# farolasbasura.net
KiCad netlist of a schematic drawn in EAGLE
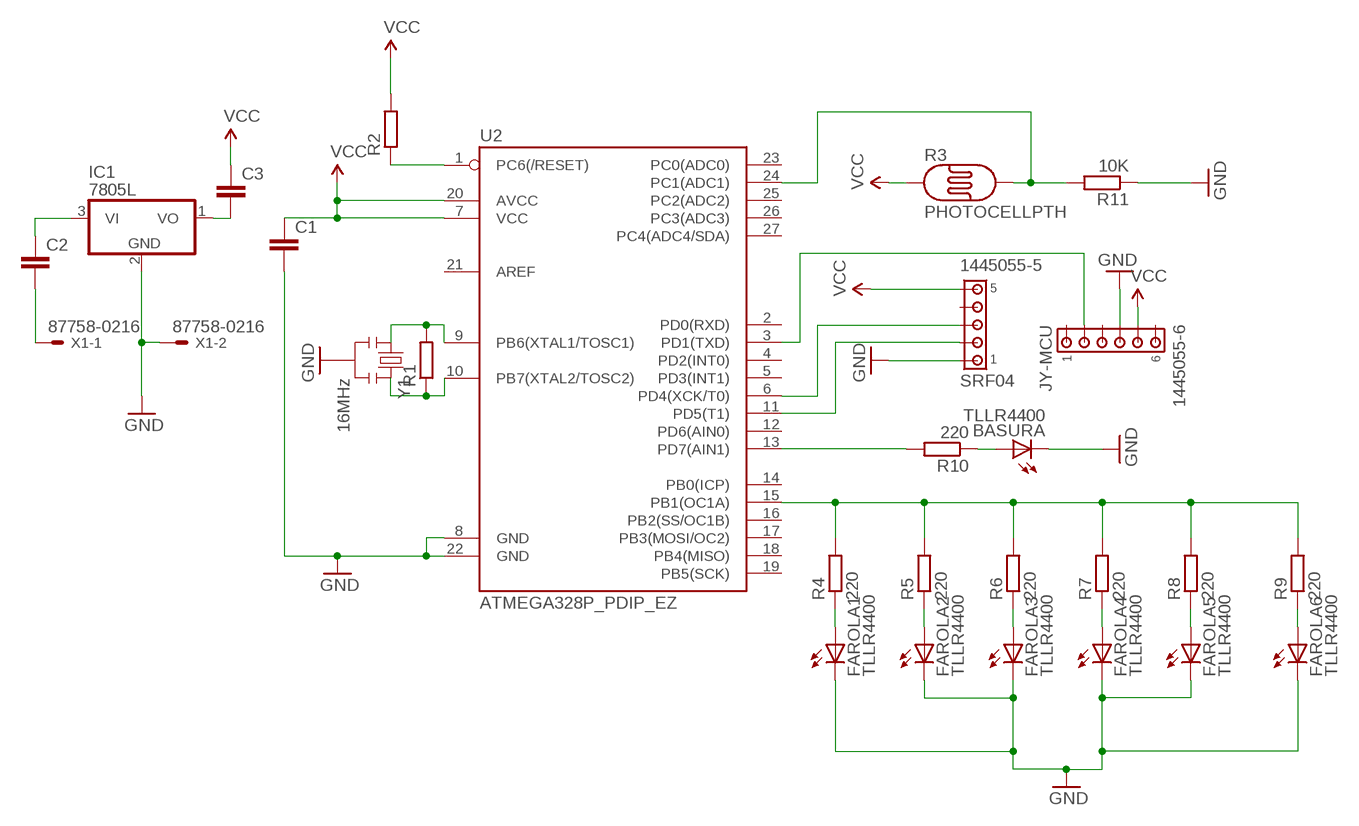
[diagram p0: schematic, sheet 1]

(export (version "E")
  (design (tool "Eeschema 10.0.6"))
  (components
    (comp (ref "BASURA")
      (value "TLLR4400")
      (footprint "eagle-import:LED3MM")
      (fields (field (name "MF") "VISHAY SEMICONDUCTOR"))
      (libsource (lib "eagle-import") (part "TLLR4400"))
    )
    (comp (ref "C1")
      (value "C-EU050-025X075")
      (footprint "eagle-import:C050-025X075")
      (libsource (lib "eagle-import") (part "C-EU050-025X075"))
    )
    (comp (ref "C2")
      (value "C-EU050-025X075")
      (footprint "eagle-import:C050-025X075")
      (libsource (lib "eagle-import") (part "C-EU050-025X075"))
    )
    (comp (ref "C3")
      (value "C-EU050-025X075")
      (footprint "eagle-import:C050-025X075")
      (libsource (lib "eagle-import") (part "C-EU050-025X075"))
    )
    (comp (ref "FAROLA1")
      (value "TLLR4400")
      (footprint "eagle-import:LED3MM")
      (fields (field (name "MF") "VISHAY SEMICONDUCTOR"))
      (libsource (lib "eagle-import") (part "TLLR4400"))
    )
    (comp (ref "FAROLA2")
      (value "TLLR4400")
      (footprint "eagle-import:LED3MM")
      (fields (field (name "MF") "VISHAY SEMICONDUCTOR"))
      (libsource (lib "eagle-import") (part "TLLR4400"))
    )
    (comp (ref "FAROLA3")
      (value "TLLR4400")
      (footprint "eagle-import:LED3MM")
      (fields (field (name "MF") "VISHAY SEMICONDUCTOR"))
      (libsource (lib "eagle-import") (part "TLLR4400"))
    )
    (comp (ref "FAROLA4")
      (value "TLLR4400")
      (footprint "eagle-import:LED3MM")
      (fields (field (name "MF") "VISHAY SEMICONDUCTOR"))
      (libsource (lib "eagle-import") (part "TLLR4400"))
    )
    (comp (ref "FAROLA5")
      (value "TLLR4400")
      (footprint "eagle-import:LED3MM")
      (fields (field (name "MF") "VISHAY SEMICONDUCTOR"))
      (libsource (lib "eagle-import") (part "TLLR4400"))
    )
    (comp (ref "FAROLA6")
      (value "TLLR4400")
      (footprint "eagle-import:LED3MM")
      (fields (field (name "MF") "VISHAY SEMICONDUCTOR"))
      (libsource (lib "eagle-import") (part "TLLR4400"))
    )
    (comp (ref "IC1")
      (value "7805L")
      (footprint "eagle-import:TO92")
      (libsource (lib "eagle-import") (part "78L05"))
    )
    (comp (ref "JY-MCU")
      (value "1445055-6")
      (footprint "eagle-import:1445055-6")
      (libsource (lib "eagle-import") (part "1445055-6"))
    )
    (comp (ref "R1")
      (value "R-EU_0204/7")
      (footprint "eagle-import:0204_7")
      (libsource (lib "eagle-import") (part "R-EU_0204/7"))
    )
    (comp (ref "R2")
      (value "R-EU_0204/7")
      (footprint "eagle-import:0204_7")
      (libsource (lib "eagle-import") (part "R-EU_0204/7"))
    )
    (comp (ref "R3")
      (value "PHOTOCELLPTH")
      (footprint "eagle-import:PHOTOCELL")
      (libsource (lib "eagle-import") (part "PHOTOCELLPTH"))
    )
    (comp (ref "R4")
      (value "220")
      (footprint "eagle-import:0204_7")
      (libsource (lib "eagle-import") (part "R-EU_0204/7"))
    )
    (comp (ref "R5")
      (value "220")
      (footprint "eagle-import:0204_7")
      (libsource (lib "eagle-import") (part "R-EU_0204/7"))
    )
    (comp (ref "R6")
      (value "220")
      (footprint "eagle-import:0204_7")
      (libsource (lib "eagle-import") (part "R-EU_0204/7"))
    )
    (comp (ref "R7")
      (value "220")
      (footprint "eagle-import:0204_7")
      (libsource (lib "eagle-import") (part "R-EU_0204/7"))
    )
    (comp (ref "R8")
      (value "220")
      (footprint "eagle-import:0204_7")
      (libsource (lib "eagle-import") (part "R-EU_0204/7"))
    )
    (comp (ref "R9")
      (value "220")
      (footprint "eagle-import:0204_7")
      (libsource (lib "eagle-import") (part "R-EU_0204/7"))
    )
    (comp (ref "R10")
      (value "220")
      (footprint "eagle-import:0204_7")
      (libsource (lib "eagle-import") (part "R-EU_0204/7"))
    )
    (comp (ref "R11")
      (value "10K")
      (footprint "eagle-import:0204_7")
      (libsource (lib "eagle-import") (part "R-EU_0204/7"))
    )
    (comp (ref "SRF04")
      (value "1445055-5")
      (footprint "eagle-import:1445055-5")
      (libsource (lib "eagle-import") (part "1445055-5"))
    )
    (comp (ref "U2")
      (value "ATMEGA328P_PDIP_EZ")
      (footprint "eagle-import:DIL28-EZ")
      (libsource (lib "eagle-import") (part "ATMEGA328P_PDIP_EZ"))
    )
    (comp (ref "X1")
      (value "87758-0216")
      (footprint "eagle-import:87758-0216")
      (libsource (lib "eagle-import") (part "87758-0216"))
    )
    (comp (ref "Y1")
      (value "16MHz")
      (footprint "eagle-import:RESONATOR-SMD")
      (libsource (lib "eagle-import") (part "RESONATOR16MHZ"))
    )
  )
  (nets
    (net (code "1") (name "GND") (class "Default")
      (node (ref "BASURA") (pin "K") (pinfunction "C_K") (pintype "passive"))
      (node (ref "C1") (pin "2") (pinfunction "2_2") (pintype "passive"))
      (node (ref "FAROLA1") (pin "K") (pinfunction "C_K") (pintype "passive"))
      (node (ref "FAROLA2") (pin "K") (pinfunction "C_K") (pintype "passive"))
      (node (ref "FAROLA3") (pin "K") (pinfunction "C_K") (pintype "passive"))
      (node (ref "FAROLA4") (pin "K") (pinfunction "C_K") (pintype "passive"))
      (node (ref "FAROLA5") (pin "K") (pinfunction "C_K") (pintype "passive"))
      (node (ref "FAROLA6") (pin "K") (pinfunction "C_K") (pintype "passive"))
      (node (ref "IC1") (pin "2") (pinfunction "GND_2") (pintype "passive"))
      (node (ref "JY-MCU") (pin "4") (pinfunction "4_4") (pintype "passive"))
      (node (ref "R11") (pin "1") (pinfunction "1_1") (pintype "passive"))
      (node (ref "SRF04") (pin "1") (pinfunction "1_1") (pintype "passive"))
      (node (ref "U2") (pin "22") (pinfunction "GND_22") (pintype "bidirectional"))
      (node (ref "U2") (pin "8") (pinfunction "GND_8") (pintype "bidirectional"))
      (node (ref "X1") (pin "2") (pinfunction "S_2") (pintype "passive"))
      (node (ref "Y1") (pin "2") (pinfunction "2_2") (pintype "passive"))
    )
    (net (code "2") (name "Net-(BASURA-PadA)") (class "Default")
      (node (ref "BASURA") (pin "A") (pinfunction "A_A") (pintype "passive"))
      (node (ref "R10") (pin "1") (pinfunction "1_1") (pintype "passive"))
    )
    (net (code "3") (name "Net-(FAROLA1-PadA)") (class "Default")
      (node (ref "FAROLA1") (pin "A") (pinfunction "A_A") (pintype "passive"))
      (node (ref "R4") (pin "1") (pinfunction "1_1") (pintype "passive"))
    )
    (net (code "4") (name "Net-(FAROLA2-PadA)") (class "Default")
      (node (ref "FAROLA2") (pin "A") (pinfunction "A_A") (pintype "passive"))
      (node (ref "R5") (pin "1") (pinfunction "1_1") (pintype "passive"))
    )
    (net (code "5") (name "Net-(FAROLA3-PadA)") (class "Default")
      (node (ref "FAROLA3") (pin "A") (pinfunction "A_A") (pintype "passive"))
      (node (ref "R6") (pin "1") (pinfunction "1_1") (pintype "passive"))
    )
    (net (code "6") (name "Net-(FAROLA4-PadA)") (class "Default")
      (node (ref "FAROLA4") (pin "A") (pinfunction "A_A") (pintype "passive"))
      (node (ref "R7") (pin "1") (pinfunction "1_1") (pintype "passive"))
    )
    (net (code "7") (name "Net-(FAROLA5-PadA)") (class "Default")
      (node (ref "FAROLA5") (pin "A") (pinfunction "A_A") (pintype "passive"))
      (node (ref "R8") (pin "1") (pinfunction "1_1") (pintype "passive"))
    )
    (net (code "8") (name "Net-(FAROLA6-PadA)") (class "Default")
      (node (ref "FAROLA6") (pin "A") (pinfunction "A_A") (pintype "passive"))
      (node (ref "R9") (pin "1") (pinfunction "1_1") (pintype "passive"))
    )
    (net (code "9") (name "Net-(IC1-VI)") (class "Default")
      (node (ref "C2") (pin "1") (pinfunction "1_1") (pintype "passive"))
      (node (ref "IC1") (pin "3") (pinfunction "VI_3") (pintype "input"))
    )
    (net (code "10") (name "Net-(IC1-VO)") (class "Default")
      (node (ref "C3") (pin "2") (pinfunction "2_2") (pintype "passive"))
      (node (ref "IC1") (pin "1") (pinfunction "VO_1") (pintype "passive"))
    )
    (net (code "11") (name "Net-(R3-P$2)") (class "Default")
      (node (ref "R11") (pin "2") (pinfunction "2_2") (pintype "passive"))
      (node (ref "R3") (pin "2") (pinfunction "P$2_2") (pintype "bidirectional"))
      (node (ref "U2") (pin "24") (pinfunction "PC1(ADC1)_24") (pintype "bidirectional"))
    )
    (net (code "12") (name "Net-(U2-PB1(OC1A))") (class "Default")
      (node (ref "R4") (pin "2") (pinfunction "2_2") (pintype "passive"))
      (node (ref "R5") (pin "2") (pinfunction "2_2") (pintype "passive"))
      (node (ref "R6") (pin "2") (pinfunction "2_2") (pintype "passive"))
      (node (ref "R7") (pin "2") (pinfunction "2_2") (pintype "passive"))
      (node (ref "R8") (pin "2") (pinfunction "2_2") (pintype "passive"))
      (node (ref "R9") (pin "2") (pinfunction "2_2") (pintype "passive"))
      (node (ref "U2") (pin "15") (pinfunction "PB1(OC1A)_15") (pintype "bidirectional"))
    )
    (net (code "13") (name "Net-(U2-PB6(XTAL1{slash}TOSC1))") (class "Default")
      (node (ref "R1") (pin "2") (pinfunction "2_2") (pintype "passive"))
      (node (ref "U2") (pin "9") (pinfunction "PB6(XTAL1/TOSC1)_9") (pintype "bidirectional"))
      (node (ref "Y1") (pin "1") (pinfunction "1_1") (pintype "passive"))
    )
    (net (code "14") (name "Net-(U2-PB7(XTAL2{slash}TOSC2))") (class "Default")
      (node (ref "R1") (pin "1") (pinfunction "1_1") (pintype "passive"))
      (node (ref "U2") (pin "10") (pinfunction "PB7(XTAL2/TOSC2)_10") (pintype "bidirectional"))
      (node (ref "Y1") (pin "3") (pinfunction "3_3") (pintype "passive"))
    )
    (net (code "15") (name "Net-(U2-PC6({slash}RESET))") (class "Default")
      (node (ref "R2") (pin "1") (pinfunction "1_1") (pintype "passive"))
      (node (ref "U2") (pin "1") (pinfunction "PC6(/RESET)_1") (pintype "bidirectional"))
    )
    (net (code "16") (name "Net-(U2-PD1(TXD))") (class "Default")
      (node (ref "JY-MCU") (pin "2") (pinfunction "2_2") (pintype "passive"))
      (node (ref "U2") (pin "3") (pinfunction "PD1(TXD)_3") (pintype "bidirectional"))
    )
    (net (code "17") (name "Net-(U2-PD4(XCK{slash}T0))") (class "Default")
      (node (ref "SRF04") (pin "3") (pinfunction "3_3") (pintype "passive"))
      (node (ref "U2") (pin "6") (pinfunction "PD4(XCK/T0)_6") (pintype "bidirectional"))
    )
    (net (code "18") (name "Net-(U2-PD5(T1))") (class "Default")
      (node (ref "SRF04") (pin "2") (pinfunction "2_2") (pintype "passive"))
      (node (ref "U2") (pin "11") (pinfunction "PD5(T1)_11") (pintype "bidirectional"))
    )
    (net (code "19") (name "Net-(U2-PD7(AIN1))") (class "Default")
      (node (ref "R10") (pin "2") (pinfunction "2_2") (pintype "passive"))
      (node (ref "U2") (pin "13") (pinfunction "PD7(AIN1)_13") (pintype "bidirectional"))
    )
    (net (code "20") (name "Net-(X1A-S)") (class "Default")
      (node (ref "C2") (pin "2") (pinfunction "2_2") (pintype "passive"))
      (node (ref "X1") (pin "1") (pinfunction "S_1") (pintype "passive"))
    )
    (net (code "21") (name "VCC") (class "Default")
      (node (ref "C1") (pin "1") (pinfunction "1_1") (pintype "passive"))
      (node (ref "C3") (pin "1") (pinfunction "1_1") (pintype "passive"))
      (node (ref "JY-MCU") (pin "5") (pinfunction "5_5") (pintype "passive"))
      (node (ref "R2") (pin "2") (pinfunction "2_2") (pintype "passive"))
      (node (ref "R3") (pin "1") (pinfunction "P$1_1") (pintype "bidirectional"))
      (node (ref "SRF04") (pin "5") (pinfunction "5_5") (pintype "passive"))
      (node (ref "U2") (pin "20") (pinfunction "AVCC_20") (pintype "bidirectional"))
      (node (ref "U2") (pin "7") (pinfunction "VCC_7") (pintype "bidirectional"))
    )
    (net (code "22") (name "unconnected-(JY-MCU-Pad1)") (class "Default")
      (node (ref "JY-MCU") (pin "1") (pinfunction "1_1") (pintype "passive"))
    )
    (net (code "23") (name "unconnected-(JY-MCU-Pad3)") (class "Default")
      (node (ref "JY-MCU") (pin "3") (pinfunction "3_3") (pintype "passive"))
    )
    (net (code "24") (name "unconnected-(JY-MCU-Pad6)") (class "Default")
      (node (ref "JY-MCU") (pin "6") (pinfunction "6_6") (pintype "passive"))
    )
    (net (code "25") (name "unconnected-(SRF04-Pad4)") (class "Default")
      (node (ref "SRF04") (pin "4") (pinfunction "4_4") (pintype "passive"))
    )
    (net (code "26") (name "unconnected-(U2-AREF-Pad21)") (class "Default")
      (node (ref "U2") (pin "21") (pinfunction "AREF_21") (pintype "bidirectional"))
    )
    (net (code "27") (name "unconnected-(U2-PB0(ICP)-Pad14)") (class "Default")
      (node (ref "U2") (pin "14") (pinfunction "PB0(ICP)_14") (pintype "bidirectional"))
    )
    (net (code "28") (name "unconnected-(U2-PB2(SS{slash}OC1B)-Pad16)") (class "Default")
      (node (ref "U2") (pin "16") (pinfunction "PB2(SS/OC1B)_16") (pintype "bidirectional"))
    )
    (net (code "29") (name "unconnected-(U2-PB3(MOSI{slash}OC2)-Pad17)") (class "Default")
      (node (ref "U2") (pin "17") (pinfunction "PB3(MOSI/OC2)_17") (pintype "bidirectional"))
    )
    (net (code "30") (name "unconnected-(U2-PB4(MISO)-Pad18)") (class "Default")
      (node (ref "U2") (pin "18") (pinfunction "PB4(MISO)_18") (pintype "bidirectional"))
    )
    (net (code "31") (name "unconnected-(U2-PB5(SCK)-Pad19)") (class "Default")
      (node (ref "U2") (pin "19") (pinfunction "PB5(SCK)_19") (pintype "bidirectional"))
    )
    (net (code "32") (name "unconnected-(U2-PC0(ADC0)-Pad23)") (class "Default")
      (node (ref "U2") (pin "23") (pinfunction "PC0(ADC0)_23") (pintype "bidirectional"))
    )
    (net (code "33") (name "unconnected-(U2-PC2(ADC2)-Pad25)") (class "Default")
      (node (ref "U2") (pin "25") (pinfunction "PC2(ADC2)_25") (pintype "bidirectional"))
    )
    (net (code "34") (name "unconnected-(U2-PC3(ADC3)-Pad26)") (class "Default")
      (node (ref "U2") (pin "26") (pinfunction "PC3(ADC3)_26") (pintype "bidirectional"))
    )
    (net (code "35") (name "unconnected-(U2-PC4(ADC4{slash}SDA)-Pad27)") (class "Default")
      (node (ref "U2") (pin "27") (pinfunction "PC4(ADC4/SDA)_27") (pintype "bidirectional"))
    )
    (net (code "36") (name "unconnected-(U2-PD0(RXD)-Pad2)") (class "Default")
      (node (ref "U2") (pin "2") (pinfunction "PD0(RXD)_2") (pintype "bidirectional"))
    )
    (net (code "37") (name "unconnected-(U2-PD2(INT0)-Pad4)") (class "Default")
      (node (ref "U2") (pin "4") (pinfunction "PD2(INT0)_4") (pintype "bidirectional"))
    )
    (net (code "38") (name "unconnected-(U2-PD3(INT1)-Pad5)") (class "Default")
      (node (ref "U2") (pin "5") (pinfunction "PD3(INT1)_5") (pintype "bidirectional"))
    )
    (net (code "39") (name "unconnected-(U2-PD6(AIN0)-Pad12)") (class "Default")
      (node (ref "U2") (pin "12") (pinfunction "PD6(AIN0)_12") (pintype "bidirectional"))
    )
  )
)
